# design.net
KiCad netlist of a schematic drawn in Altium Designer
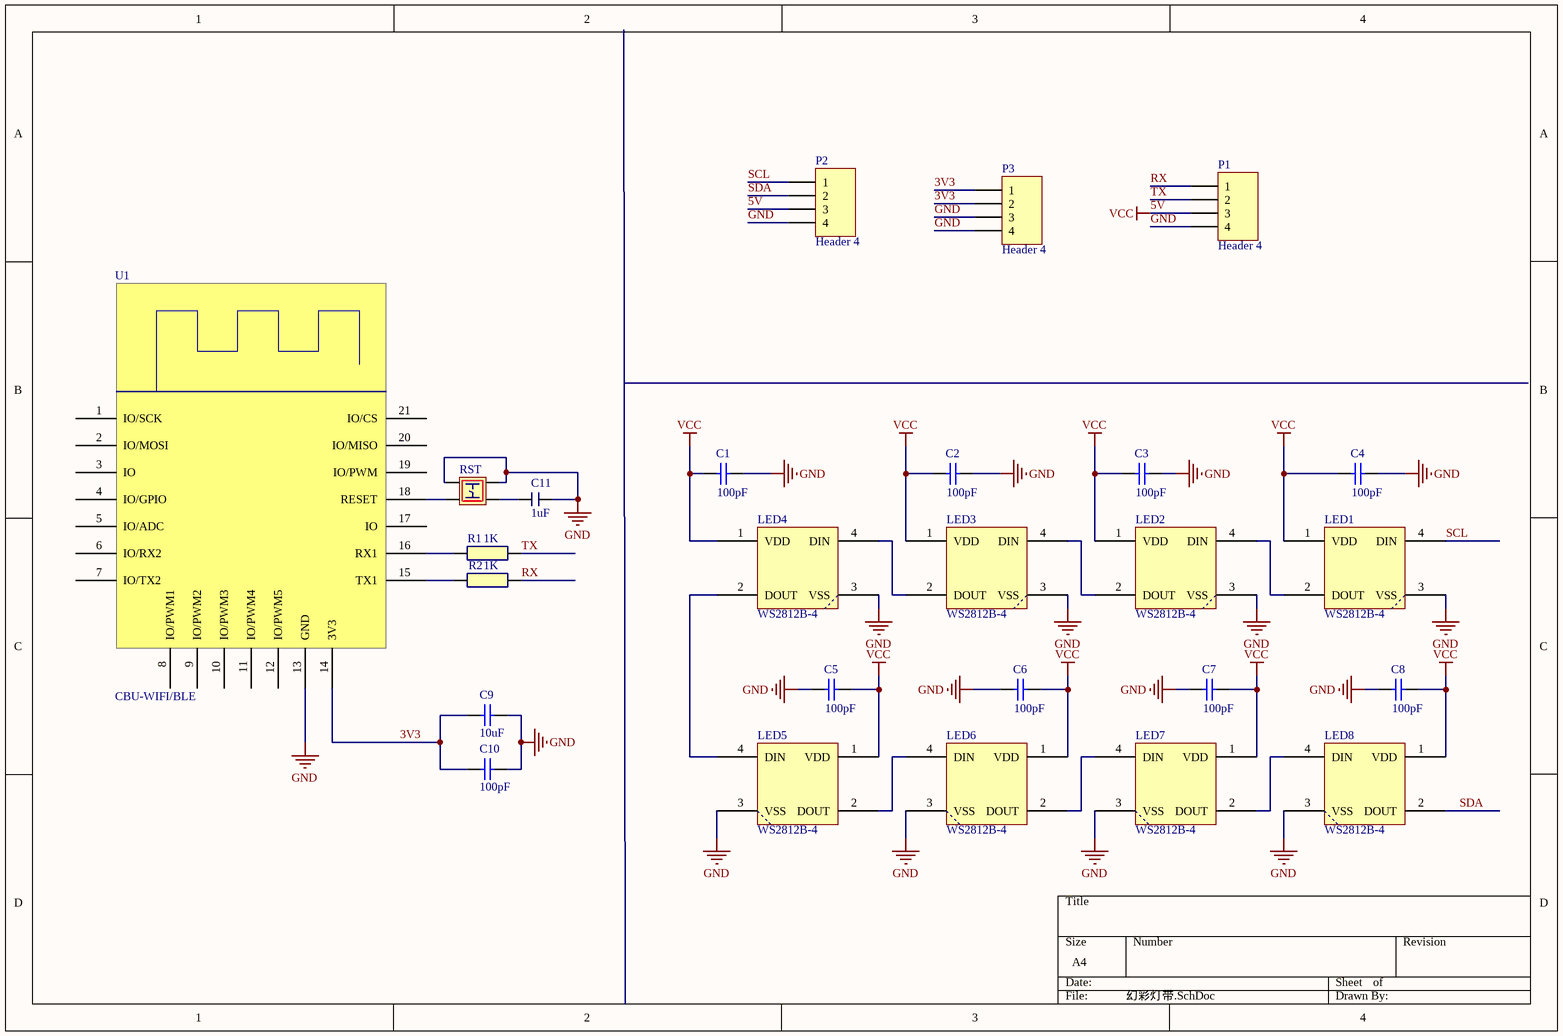
[diagram p0: 幻彩灯带.SchDoc]

(export (version "E")
  (design (tool "Eeschema 10.0.6"))
  (components
    (comp (ref "C1")
      (value "100pF")
      (footprint "6-0805_N")
      (description "Capacitor")
      (fields (field (name "Comment") "0.1uF") (field (name "PUBLISHER") "Altium Limited"))
      (libsource (lib "Miscellaneous Devices") (part "Cap"))
    )
    (comp (ref "C2")
      (value "100pF")
      (footprint "6-0805_N")
      (description "Capacitor")
      (fields (field (name "Comment") "Cap") (field (name "PUBLISHER") "Altium Limited"))
      (libsource (lib "Miscellaneous Devices") (part "Cap"))
    )
    (comp (ref "C3")
      (value "100pF")
      (footprint "6-0805_N")
      (description "Capacitor")
      (fields (field (name "Comment") "Cap") (field (name "PUBLISHER") "Altium Limited"))
      (libsource (lib "Miscellaneous Devices") (part "Cap"))
    )
    (comp (ref "C4")
      (value "100pF")
      (footprint "6-0805_N")
      (description "Capacitor")
      (fields (field (name "Comment") "Cap") (field (name "PUBLISHER") "Altium Limited"))
      (libsource (lib "Miscellaneous Devices") (part "Cap"))
    )
    (comp (ref "C5")
      (value "100pF")
      (footprint "6-0805_N")
      (description "Capacitor")
      (fields (field (name "Comment") "0.1uF") (field (name "PUBLISHER") "Altium Limited"))
      (libsource (lib "Miscellaneous Devices") (part "Cap"))
    )
    (comp (ref "C6")
      (value "100pF")
      (footprint "Miscellaneous Devices:6-0805_N")
      (description "Capacitor")
      (fields (field (name "Comment") "0.1uF") (field (name "PUBLISHER") "Altium Limited"))
      (libsource (lib "Miscellaneous Devices") (part "Cap"))
    )
    (comp (ref "C7")
      (value "100pF")
      (footprint "6-0805_N")
      (description "Capacitor")
      (fields (field (name "Comment") "0.1uF") (field (name "PUBLISHER") "Altium Limited"))
      (libsource (lib "Miscellaneous Devices") (part "Cap"))
    )
    (comp (ref "C8")
      (value "100pF")
      (footprint "6-0805_N")
      (description "Capacitor")
      (fields (field (name "Comment") "0.1uF") (field (name "PUBLISHER") "Altium Limited"))
      (libsource (lib "Miscellaneous Devices") (part "Cap"))
    )
    (comp (ref "C9")
      (value "10uF")
      (footprint "6-0805_N")
      (description "Capacitor")
      (fields (field (name "PUBLISHER") "Altium Limited"))
      (libsource (lib "Miscellaneous Devices") (part "Cap"))
    )
    (comp (ref "C10")
      (value "100pF")
      (footprint "6-0805_N")
      (description "Capacitor")
      (fields (field (name "PUBLISHER") "Altium Limited"))
      (libsource (lib "Miscellaneous Devices") (part "Cap"))
    )
    (comp (ref "C11") (value "1uF") (footprint "C 0805_L") (libsource (lib "my") (part "CAP")))
    (comp (ref "LED1") (value "WS2812B-4") (footprint "LED") (libsource (lib "my") (part "LED")))
    (comp (ref "LED2") (value "WS2812B-4") (footprint "LED") (libsource (lib "my") (part "LED")))
    (comp (ref "LED3") (value "WS2812B-4") (footprint "LED") (libsource (lib "my") (part "LED")))
    (comp (ref "LED4") (value "WS2812B-4") (footprint "LED") (libsource (lib "my") (part "LED")))
    (comp (ref "LED5") (value "WS2812B-4") (footprint "LED") (libsource (lib "") (part "LED_1")))
    (comp (ref "LED6") (value "WS2812B-4") (footprint "LED") (libsource (lib "") (part "LED_1")))
    (comp (ref "LED7") (value "WS2812B-4") (footprint "LED") (libsource (lib "") (part "LED_1")))
    (comp (ref "LED8") (value "WS2812B-4") (footprint "LED") (libsource (lib "") (part "LED_1")))
    (comp (ref "P1")
      (value "Header 4")
      (footprint "HDR1X4")
      (description "Header, 4-Pin")
      (fields (field (name "PUBLISHER") "Altium Limited"))
      (libsource (lib "Miscellaneous Connectors") (part "Header 4"))
    )
    (comp (ref "P2")
      (value "Header 4")
      (footprint "HDR1X4")
      (description "Header, 4-Pin")
      (fields (field (name "PUBLISHER") "Altium Limited"))
      (libsource (lib "Miscellaneous Connectors") (part "Header 4"))
    )
    (comp (ref "P3")
      (value "Header 4")
      (footprint "HDR1X4")
      (description "Header, 4-Pin")
      (fields (field (name "PUBLISHER") "Altium Limited"))
      (libsource (lib "Miscellaneous Connectors") (part "Header 4"))
    )
    (comp (ref "R1") (value "1K") (footprint "R 0805_M") (libsource (lib "my") (part "REGISTER")))
    (comp (ref "R2") (value "1K") (footprint "R 0805_M") (libsource (lib "my") (part "REGISTER")))
    (comp (ref "RST") (value "BUTTON") (footprint "BUTTON6*6") (libsource (lib "my") (part "BUTTON")))
    (comp (ref "U1") (value "CBU-WIFI/BLE") (footprint "CBU") (libsource (lib "my") (part "CBU-WIFI/BLE")))
  )
  (nets
    (net (code "1") (name "/3V3") (class "Default")
      (node (ref "C10") (pin "1") (pinfunction "1_1") (pintype "passive"))
      (node (ref "C9") (pin "1") (pinfunction "1_1") (pintype "passive"))
      (node (ref "P3") (pin "1") (pinfunction "1_1") (pintype "passive"))
      (node (ref "P3") (pin "2") (pinfunction "2_2") (pintype "passive"))
      (node (ref "U1") (pin "14") (pinfunction "3V3_14") (pintype "passive"))
    )
    (net (code "2") (name "/RX") (class "Default")
      (node (ref "P1") (pin "1") (pinfunction "1_1") (pintype "passive"))
      (node (ref "R2") (pin "2") (pinfunction "2_2") (pintype "passive"))
    )
    (net (code "3") (name "/SCL") (class "Default")
      (node (ref "LED1") (pin "4") (pinfunction "DIN_4") (pintype "passive"))
      (node (ref "P2") (pin "1") (pinfunction "1_1") (pintype "passive"))
    )
    (net (code "4") (name "/SDA") (class "Default")
      (node (ref "LED8") (pin "2") (pinfunction "DOUT_2") (pintype "passive"))
      (node (ref "P2") (pin "2") (pinfunction "2_2") (pintype "passive"))
    )
    (net (code "5") (name "/TX") (class "Default")
      (node (ref "P1") (pin "2") (pinfunction "2_2") (pintype "passive"))
      (node (ref "R1") (pin "2") (pinfunction "2_2") (pintype "passive"))
    )
    (net (code "6") (name "GND") (class "Default")
      (node (ref "C1") (pin "2") (pinfunction "2_2") (pintype "passive"))
      (node (ref "C10") (pin "2") (pinfunction "2_2") (pintype "passive"))
      (node (ref "C11") (pin "2") (pinfunction "2_2") (pintype "passive"))
      (node (ref "C2") (pin "2") (pinfunction "2_2") (pintype "passive"))
      (node (ref "C3") (pin "2") (pinfunction "2_2") (pintype "passive"))
      (node (ref "C4") (pin "2") (pinfunction "2_2") (pintype "passive"))
      (node (ref "C5") (pin "1") (pinfunction "1_1") (pintype "passive"))
      (node (ref "C6") (pin "1") (pinfunction "1_1") (pintype "passive"))
      (node (ref "C7") (pin "1") (pinfunction "1_1") (pintype "passive"))
      (node (ref "C8") (pin "1") (pinfunction "1_1") (pintype "passive"))
      (node (ref "C9") (pin "2") (pinfunction "2_2") (pintype "passive"))
      (node (ref "LED1") (pin "3") (pinfunction "VSS_3") (pintype "passive"))
      (node (ref "LED2") (pin "3") (pinfunction "VSS_3") (pintype "passive"))
      (node (ref "LED3") (pin "3") (pinfunction "VSS_3") (pintype "passive"))
      (node (ref "LED4") (pin "3") (pinfunction "VSS_3") (pintype "passive"))
      (node (ref "LED5") (pin "3") (pinfunction "VSS_3") (pintype "passive"))
      (node (ref "LED6") (pin "3") (pinfunction "VSS_3") (pintype "passive"))
      (node (ref "LED7") (pin "3") (pinfunction "VSS_3") (pintype "passive"))
      (node (ref "LED8") (pin "3") (pinfunction "VSS_3") (pintype "passive"))
      (node (ref "P1") (pin "4") (pinfunction "4_4") (pintype "passive"))
      (node (ref "P2") (pin "4") (pinfunction "4_4") (pintype "passive"))
      (node (ref "P3") (pin "3") (pinfunction "3_3") (pintype "passive"))
      (node (ref "P3") (pin "4") (pinfunction "4_4") (pintype "passive"))
      (node (ref "RST") (pin "1") (pinfunction "1_1") (pintype "passive"))
      (node (ref "U1") (pin "13") (pinfunction "GND_13") (pintype "passive"))
    )
    (net (code "7") (name "Net-(C11-Pad1)") (class "Default")
      (node (ref "C11") (pin "1") (pinfunction "1_1") (pintype "passive"))
      (node (ref "RST") (pin "2") (pinfunction "2_2") (pintype "passive"))
    )
    (net (code "8") (name "Net-(LED1-DOUT)") (class "Default")
      (node (ref "LED1") (pin "2") (pinfunction "DOUT_2") (pintype "passive"))
      (node (ref "LED2") (pin "4") (pinfunction "DIN_4") (pintype "passive"))
    )
    (net (code "9") (name "Net-(LED2-DOUT)") (class "Default")
      (node (ref "LED2") (pin "2") (pinfunction "DOUT_2") (pintype "passive"))
      (node (ref "LED3") (pin "4") (pinfunction "DIN_4") (pintype "passive"))
    )
    (net (code "10") (name "Net-(LED3-DOUT)") (class "Default")
      (node (ref "LED3") (pin "2") (pinfunction "DOUT_2") (pintype "passive"))
      (node (ref "LED4") (pin "4") (pinfunction "DIN_4") (pintype "passive"))
    )
    (net (code "11") (name "Net-(LED4-DOUT)") (class "Default")
      (node (ref "LED4") (pin "2") (pinfunction "DOUT_2") (pintype "passive"))
      (node (ref "LED5") (pin "4") (pinfunction "DIN_4") (pintype "passive"))
    )
    (net (code "12") (name "Net-(LED5-DOUT)") (class "Default")
      (node (ref "LED5") (pin "2") (pinfunction "DOUT_2") (pintype "passive"))
      (node (ref "LED6") (pin "4") (pinfunction "DIN_4") (pintype "passive"))
    )
    (net (code "13") (name "Net-(LED6-DOUT)") (class "Default")
      (node (ref "LED6") (pin "2") (pinfunction "DOUT_2") (pintype "passive"))
      (node (ref "LED7") (pin "4") (pinfunction "DIN_4") (pintype "passive"))
    )
    (net (code "14") (name "Net-(LED7-DOUT)") (class "Default")
      (node (ref "LED7") (pin "2") (pinfunction "DOUT_2") (pintype "passive"))
      (node (ref "LED8") (pin "4") (pinfunction "DIN_4") (pintype "passive"))
    )
    (net (code "15") (name "Net-(U1-RESET)") (class "Default")
      (node (ref "RST") (pin "2") (pinfunction "2_2") (pintype "passive"))
      (node (ref "U1") (pin "18") (pinfunction "RESET_18") (pintype "passive"))
    )
    (net (code "16") (name "Net-(U1-RX1)") (class "Default")
      (node (ref "R1") (pin "1") (pinfunction "1_1") (pintype "passive"))
      (node (ref "U1") (pin "16") (pinfunction "RX1_16") (pintype "passive"))
    )
    (net (code "17") (name "Net-(U1-TX1)") (class "Default")
      (node (ref "R2") (pin "1") (pinfunction "1_1") (pintype "passive"))
      (node (ref "U1") (pin "15") (pinfunction "TX1_15") (pintype "passive"))
    )
    (net (code "18") (name "VCC") (class "Default")
      (node (ref "C1") (pin "1") (pinfunction "1_1") (pintype "passive"))
      (node (ref "C2") (pin "1") (pinfunction "1_1") (pintype "passive"))
      (node (ref "C3") (pin "1") (pinfunction "1_1") (pintype "passive"))
      (node (ref "C4") (pin "1") (pinfunction "1_1") (pintype "passive"))
      (node (ref "C5") (pin "2") (pinfunction "2_2") (pintype "passive"))
      (node (ref "C6") (pin "2") (pinfunction "2_2") (pintype "passive"))
      (node (ref "C7") (pin "2") (pinfunction "2_2") (pintype "passive"))
      (node (ref "C8") (pin "2") (pinfunction "2_2") (pintype "passive"))
      (node (ref "LED1") (pin "1") (pinfunction "VDD_1") (pintype "passive"))
      (node (ref "LED2") (pin "1") (pinfunction "VDD_1") (pintype "passive"))
      (node (ref "LED3") (pin "1") (pinfunction "VDD_1") (pintype "passive"))
      (node (ref "LED4") (pin "1") (pinfunction "VDD_1") (pintype "passive"))
      (node (ref "LED5") (pin "1") (pinfunction "VDD_1") (pintype "passive"))
      (node (ref "LED6") (pin "1") (pinfunction "VDD_1") (pintype "passive"))
      (node (ref "LED7") (pin "1") (pinfunction "VDD_1") (pintype "passive"))
      (node (ref "LED8") (pin "1") (pinfunction "VDD_1") (pintype "passive"))
      (node (ref "P1") (pin "3") (pinfunction "3_3") (pintype "passive"))
      (node (ref "P2") (pin "3") (pinfunction "3_3") (pintype "passive"))
    )
    (net (code "19") (name "unconnected-(U1-IO-Pad3)") (class "Default")
      (node (ref "U1") (pin "3") (pinfunction "IO_3") (pintype "passive"))
    )
    (net (code "20") (name "unconnected-(U1-IO-Pad17)") (class "Default")
      (node (ref "U1") (pin "17") (pinfunction "IO_17") (pintype "passive"))
    )
    (net (code "21") (name "unconnected-(U1-IO{slash}ADC-Pad5)") (class "Default")
      (node (ref "U1") (pin "5") (pinfunction "IO/ADC_5") (pintype "passive"))
    )
    (net (code "22") (name "unconnected-(U1-IO{slash}CS-Pad21)") (class "Default")
      (node (ref "U1") (pin "21") (pinfunction "IO/CS_21") (pintype "passive"))
    )
    (net (code "23") (name "unconnected-(U1-IO{slash}GPIO-Pad4)") (class "Default")
      (node (ref "U1") (pin "4") (pinfunction "IO/GPIO_4") (pintype "passive"))
    )
    (net (code "24") (name "unconnected-(U1-IO{slash}MISO-Pad20)") (class "Default")
      (node (ref "U1") (pin "20") (pinfunction "IO/MISO_20") (pintype "passive"))
    )
    (net (code "25") (name "unconnected-(U1-IO{slash}MOSI-Pad2)") (class "Default")
      (node (ref "U1") (pin "2") (pinfunction "IO/MOSI_2") (pintype "passive"))
    )
    (net (code "26") (name "unconnected-(U1-IO{slash}PWM-Pad19)") (class "Default")
      (node (ref "U1") (pin "19") (pinfunction "IO/PWM_19") (pintype "passive"))
    )
    (net (code "27") (name "unconnected-(U1-IO{slash}PWM1-Pad8)") (class "Default")
      (node (ref "U1") (pin "8") (pinfunction "IO/PWM1_8") (pintype "passive"))
    )
    (net (code "28") (name "unconnected-(U1-IO{slash}PWM2-Pad9)") (class "Default")
      (node (ref "U1") (pin "9") (pinfunction "IO/PWM2_9") (pintype "passive"))
    )
    (net (code "29") (name "unconnected-(U1-IO{slash}PWM3-Pad10)") (class "Default")
      (node (ref "U1") (pin "10") (pinfunction "IO/PWM3_10") (pintype "passive"))
    )
    (net (code "30") (name "unconnected-(U1-IO{slash}PWM4-Pad11)") (class "Default")
      (node (ref "U1") (pin "11") (pinfunction "IO/PWM4_11") (pintype "passive"))
    )
    (net (code "31") (name "unconnected-(U1-IO{slash}PWM5-Pad12)") (class "Default")
      (node (ref "U1") (pin "12") (pinfunction "IO/PWM5_12") (pintype "passive"))
    )
    (net (code "32") (name "unconnected-(U1-IO{slash}RX2-Pad6)") (class "Default")
      (node (ref "U1") (pin "6") (pinfunction "IO/RX2_6") (pintype "passive"))
    )
    (net (code "33") (name "unconnected-(U1-IO{slash}SCK-Pad1)") (class "Default")
      (node (ref "U1") (pin "1") (pinfunction "IO/SCK_1") (pintype "passive"))
    )
    (net (code "34") (name "unconnected-(U1-IO{slash}TX2-Pad7)") (class "Default")
      (node (ref "U1") (pin "7") (pinfunction "IO/TX2_7") (pintype "passive"))
    )
  )
)
